# HGD_v0_1_-20200419.net
KiCad netlist of a schematic drawn in Altium Designer
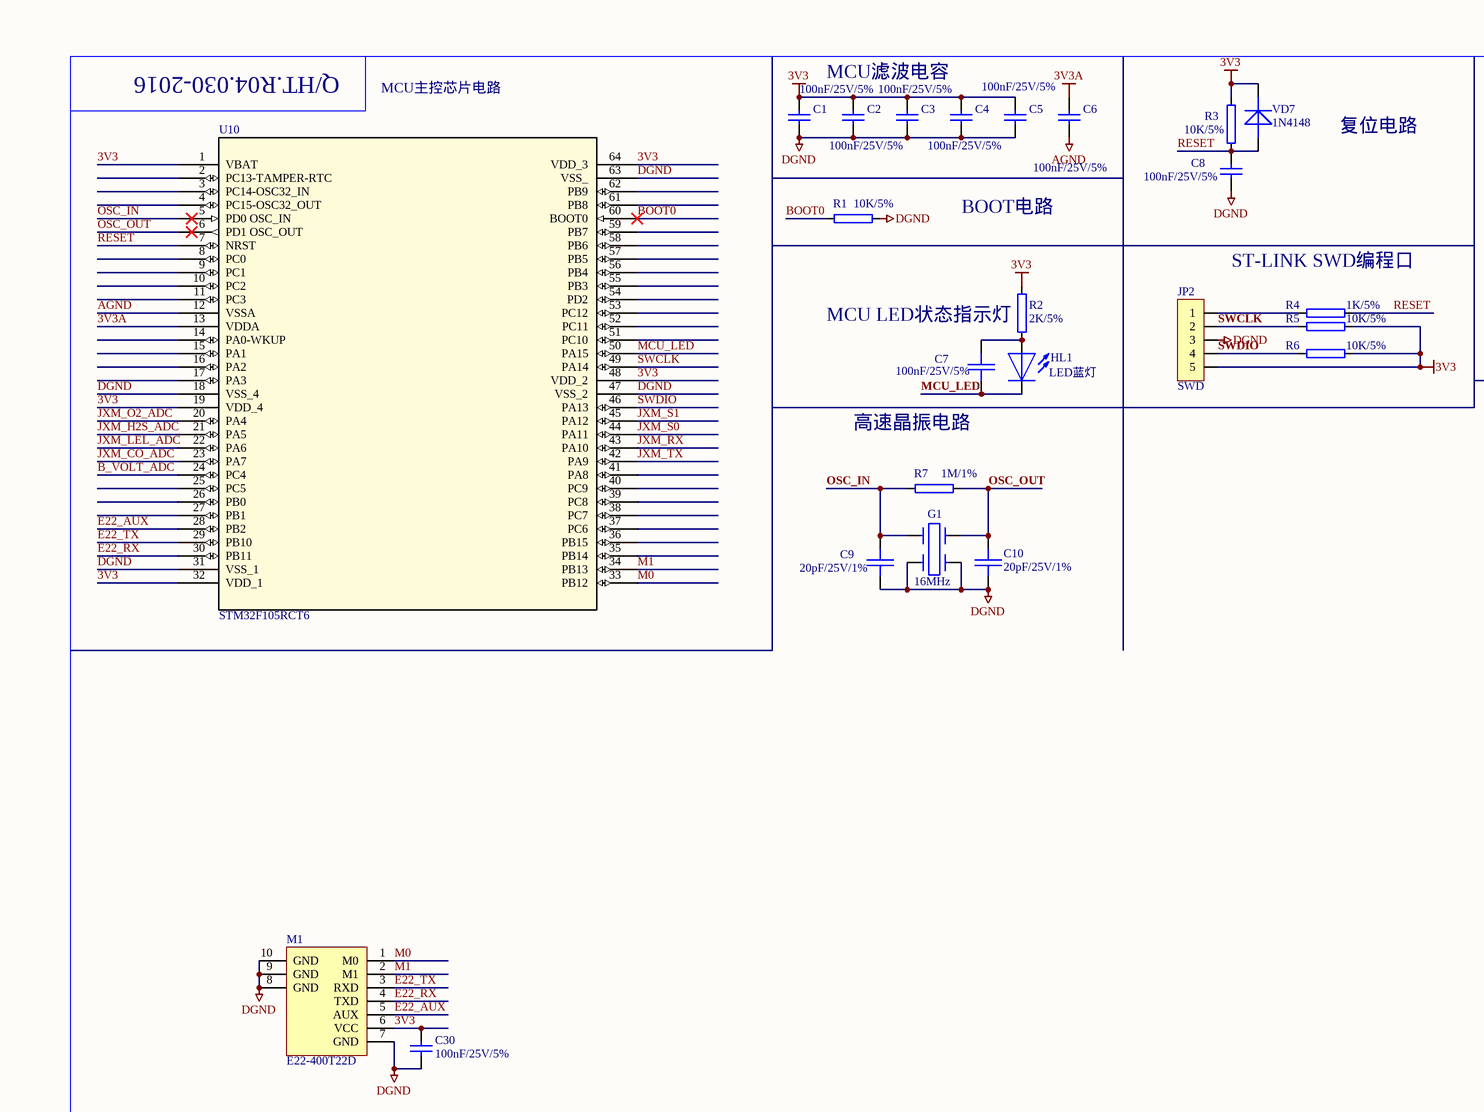
[diagram p0: HGD(v0.1)-20200419.SchDoc, top left]
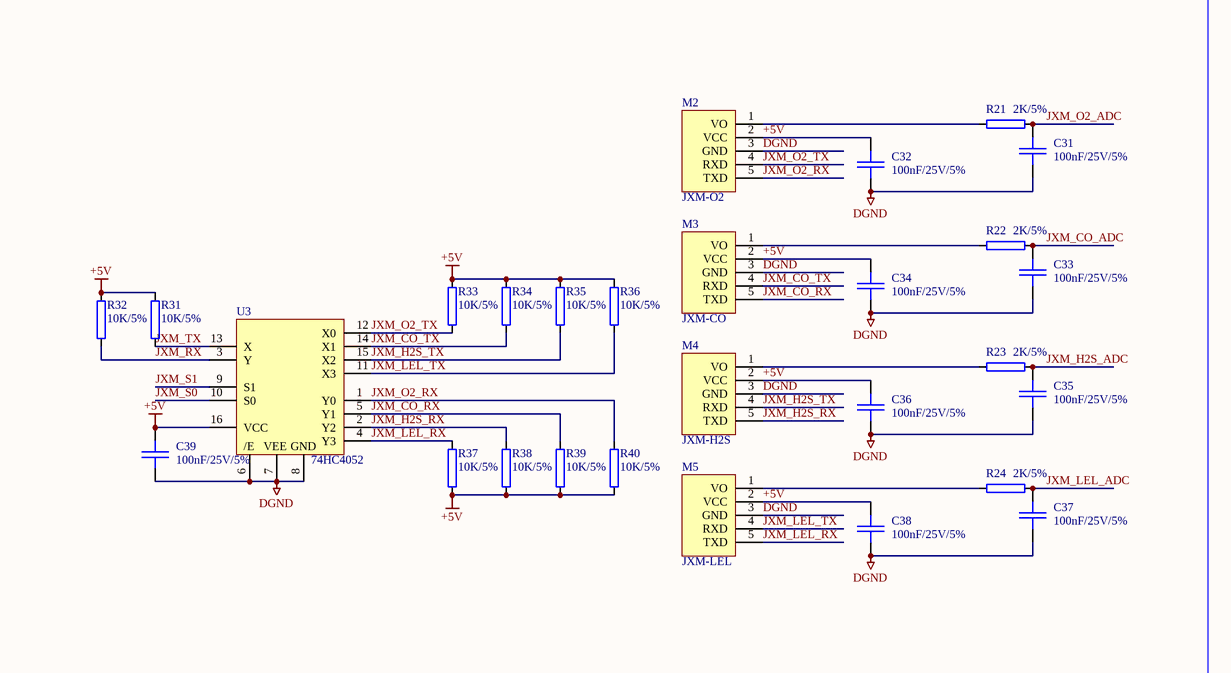
[diagram p1: HGD(v0.1)-20200419.SchDoc, top right]
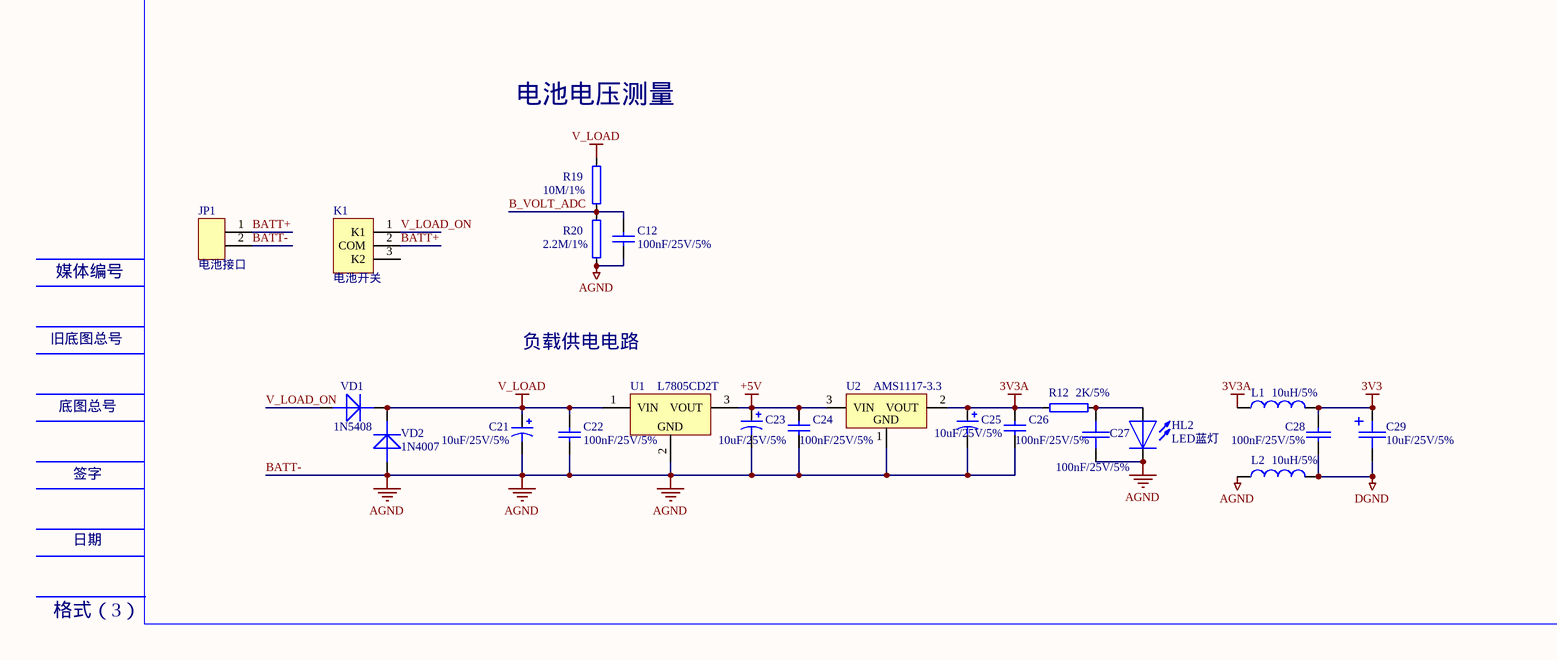
[diagram p2: HGD(v0.1)-20200419.SchDoc, bottom left]
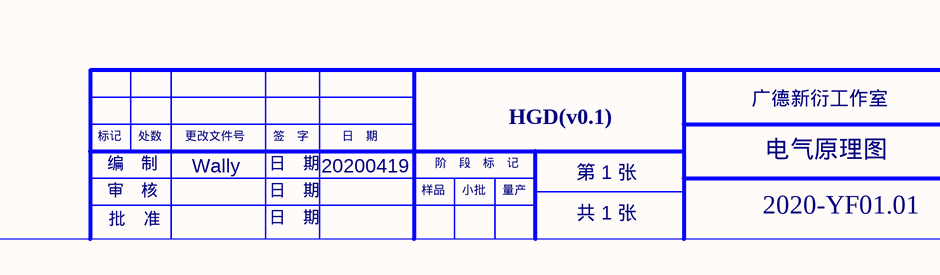
[diagram p3: HGD(v0.1)-20200419.SchDoc, bottom right]

(export (version "E")
  (design (tool "Eeschema 10.0.6"))
  (components
    (comp (ref "C1")
      (value "100nF/25V/5%")
      (footprint "C0603")
      (description "电容")
      (libsource (lib "*") (part "CAP-SMD"))
    )
    (comp (ref "C2")
      (value "100nF/25V/5%")
      (footprint "C0603")
      (description "电容")
      (libsource (lib "*") (part "CAP-SMD"))
    )
    (comp (ref "C3")
      (value "100nF/25V/5%")
      (footprint "C0603")
      (description "电容")
      (libsource (lib "*") (part "CAP-SMD"))
    )
    (comp (ref "C4")
      (value "100nF/25V/5%")
      (footprint "C0603")
      (description "电容")
      (libsource (lib "*") (part "CAP-SMD"))
    )
    (comp (ref "C5")
      (value "100nF/25V/5%")
      (footprint "C0603")
      (description "电容")
      (libsource (lib "*") (part "CAP-SMD"))
    )
    (comp (ref "C6")
      (value "100nF/25V/5%")
      (footprint "C0603")
      (description "电容")
      (libsource (lib "*") (part "CAP-SMD"))
    )
    (comp (ref "C7")
      (value "100nF/25V/5%")
      (footprint "C0603")
      (description "电容")
      (libsource (lib "*") (part "CAP"))
    )
    (comp (ref "C8")
      (value "100nF/25V/5%")
      (footprint "C0603")
      (description "电容")
      (libsource (lib "*") (part "CAP-SMD"))
    )
    (comp (ref "C9")
      (value "20pF/25V/1%")
      (footprint "C0603")
      (description "电容")
      (libsource (lib "ESSCH-Union") (part "CAP"))
    )
    (comp (ref "C10")
      (value "20pF/25V/1%")
      (footprint "C0603")
      (description "电容")
      (libsource (lib "ESSCH-Union") (part "CAP"))
    )
    (comp (ref "C12") (value "100nF/25V/5%") (footprint "C0603") (libsource (lib "*") (part "CAP-SMD")))
    (comp (ref "C21")
      (value "10uF/25V/5%")
      (footprint "C1206-1")
      (description "钽电容")
      (fields (field (name "PUBLISHER") "Altium Limited"))
      (libsource (lib "Miscellaneous Devices") (part "Cap Pol1"))
    )
    (comp (ref "C22")
      (value "100nF/25V/5%")
      (footprint "C0603")
      (description "电容")
      (fields (field (name "PUBLISHER") "Altium Limited"))
      (libsource (lib "Miscellaneous Devices") (part "Cap"))
    )
    (comp (ref "C23")
      (value "10uF/25V/5%")
      (footprint "C1206-1")
      (description "钽电容")
      (fields (field (name "PUBLISHER") "Altium Limited"))
      (libsource (lib "Miscellaneous Devices") (part "Cap Pol1"))
    )
    (comp (ref "C24")
      (value "100nF/25V/5%")
      (footprint "C0603")
      (description "电容")
      (fields (field (name "PUBLISHER") "Altium Limited"))
      (libsource (lib "Miscellaneous Devices") (part "Cap"))
    )
    (comp (ref "C25")
      (value "10uF/25V/5%")
      (footprint "C1206-1")
      (description "钽电容")
      (fields (field (name "PUBLISHER") "Altium Limited"))
      (libsource (lib "Miscellaneous Devices") (part "Cap Pol1"))
    )
    (comp (ref "C26")
      (value "100nF/25V/5%")
      (footprint "C0603")
      (description "电容")
      (fields (field (name "PUBLISHER") "Altium Limited"))
      (libsource (lib "Miscellaneous Devices") (part "Cap"))
    )
    (comp (ref "C27")
      (value "100nF/25V/5%")
      (footprint "C0603")
      (description "电容")
      (libsource (lib "*") (part "CAP"))
    )
    (comp (ref "C28")
      (value "100nF/25V/5%")
      (footprint "C0603")
      (description "电容")
      (libsource (lib "") (part "CAP_1"))
    )
    (comp (ref "C29")
      (value "10uF/25V/5%")
      (footprint "C1206-1")
      (description "钽电容")
      (libsource (lib "*") (part "ELECTRO1"))
    )
    (comp (ref "C30")
      (value "100nF/25V/5%")
      (footprint "C0603")
      (description "电容")
      (fields (field (name "PUBLISHER") "Altium Limited"))
      (libsource (lib "Miscellaneous Devices") (part "Cap"))
    )
    (comp (ref "C31")
      (value "100nF/25V/5%")
      (footprint "C0603")
      (description "电容")
      (libsource (lib "*") (part "CAP"))
    )
    (comp (ref "C32")
      (value "100nF/25V/5%")
      (footprint "C0603")
      (description "电容")
      (libsource (lib "*") (part "CAP"))
    )
    (comp (ref "C33")
      (value "100nF/25V/5%")
      (footprint "C0603")
      (description "电容")
      (libsource (lib "*") (part "CAP"))
    )
    (comp (ref "C34")
      (value "100nF/25V/5%")
      (footprint "C0603")
      (description "电容")
      (libsource (lib "*") (part "CAP"))
    )
    (comp (ref "C35")
      (value "100nF/25V/5%")
      (footprint "C0603")
      (description "电容")
      (libsource (lib "*") (part "CAP"))
    )
    (comp (ref "C36")
      (value "100nF/25V/5%")
      (footprint "C0603")
      (description "电容")
      (libsource (lib "*") (part "CAP"))
    )
    (comp (ref "C37")
      (value "100nF/25V/5%")
      (footprint "C0603")
      (description "电容")
      (libsource (lib "*") (part "CAP"))
    )
    (comp (ref "C38")
      (value "100nF/25V/5%")
      (footprint "C0603")
      (description "电容")
      (libsource (lib "*") (part "CAP"))
    )
    (comp (ref "C39")
      (value "100nF/25V/5%")
      (footprint "C0603")
      (description "电容")
      (libsource (lib "*") (part "CAP"))
    )
    (comp (ref "G1")
      (value "16MHz")
      (footprint "OSC5032")
      (description "两对电极压电晶体")
      (libsource (lib "ESSCH-Union") (part "CRYSTAL_4"))
    )
    (comp (ref "HL1")
      (value "LED蓝灯")
      (footprint "LED0603")
      (description "发光二极管")
      (libsource (lib "wypPCB_Lib") (part "发光二极管"))
    )
    (comp (ref "HL2")
      (value "LED蓝灯")
      (footprint "LED0603")
      (description "发光二极管")
      (libsource (lib "wypPCB_Lib") (part "发光二极管"))
    )
    (comp (ref "JP1")
      (value "电池接口")
      (footprint "XH2.54-LI-2P")
      (description "XH2.54-2P/PH2.0-2P插座")
      (libsource (lib "wypPCB_Lib") (part "XH2.54-2P/PH2.0-2P"))
    )
    (comp (ref "JP2")
      (value "SWD")
      (footprint "XH2.54-5AW")
      (description "XH2.54-5P直插插针")
      (libsource (lib "wypPCB_Lib") (part "JP_XH2.54-5AW"))
    )
    (comp (ref "K1")
      (value "电池开关")
      (footprint "SK-12D07")
      (description "SK-12D07：3脚2档小型拨动开关")
      (libsource (lib "wypPCB_Lib") (part "SK-12D07"))
    )
    (comp (ref "L1")
      (value "10uH/5%")
      (footprint "L0603")
      (description "电感")
      (libsource (lib "wypPCB_Lib") (part "电感"))
    )
    (comp (ref "L2")
      (value "10uH/5%")
      (footprint "L0603")
      (description "电感")
      (libsource (lib "wypPCB_Lib") (part "电感"))
    )
    (comp (ref "M1")
      (value "E22-400T22D")
      (footprint "E22-400T22D")
      (description "E22-400T22D LoRa模块")
      (libsource (lib "wypPCB_Lib") (part "E22-400T22D"))
    )
    (comp (ref "M2")
      (value "JXM-O2")
      (footprint "JXM")
      (description "JXM智能气体模组传感器")
      (libsource (lib "wypPCB_Lib") (part "JXM"))
    )
    (comp (ref "M3")
      (value "JXM-CO")
      (footprint "JXM")
      (description "JXM智能气体模组传感器")
      (libsource (lib "wypPCB_Lib") (part "JXM"))
    )
    (comp (ref "M4")
      (value "JXM-H2S")
      (footprint "JXM")
      (description "JXM智能气体模组传感器")
      (libsource (lib "wypPCB_Lib") (part "JXM"))
    )
    (comp (ref "M5")
      (value "JXM-LEL")
      (footprint "JXM")
      (description "JXM智能气体模组传感器")
      (libsource (lib "wypPCB_Lib") (part "JXM"))
    )
    (comp (ref "R1")
      (value "10K/5%")
      (footprint "R0603")
      (description "电阻")
      (libsource (lib "") (part "RES2_2"))
    )
    (comp (ref "R2")
      (value "2K/5%")
      (footprint "R0603")
      (description "电阻")
      (libsource (lib "") (part "RES2_2"))
    )
    (comp (ref "R3")
      (value "10K/5%")
      (footprint "R0603")
      (description "电阻")
      (libsource (lib "") (part "RES2_1"))
    )
    (comp (ref "R4")
      (value "1K/5%")
      (footprint "R0603")
      (description "电阻")
      (libsource (lib "") (part "RES2_1"))
    )
    (comp (ref "R5")
      (value "10K/5%")
      (footprint "R0603")
      (description "电阻")
      (libsource (lib "") (part "RES2_1"))
    )
    (comp (ref "R6")
      (value "10K/5%")
      (footprint "R0603")
      (description "电阻")
      (libsource (lib "") (part "RES2_1"))
    )
    (comp (ref "R7")
      (value "1M/1%")
      (footprint "R0603")
      (description "电阻")
      (libsource (lib "") (part "RES2_1"))
    )
    (comp (ref "R12")
      (value "2K/5%")
      (footprint "R0603")
      (description "电阻")
      (libsource (lib "") (part "RES2_2"))
    )
    (comp (ref "R19")
      (value "10M/1%")
      (footprint "R0603")
      (description "电阻")
      (libsource (lib "") (part "RES2_2"))
    )
    (comp (ref "R20")
      (value "2.2M/1%")
      (footprint "R0603")
      (description "电阻")
      (libsource (lib "") (part "RES2_2"))
    )
    (comp (ref "R21")
      (value "2K/5%")
      (footprint "R0603")
      (description "电阻")
      (libsource (lib "") (part "RES2_2"))
    )
    (comp (ref "R22")
      (value "2K/5%")
      (footprint "R0603")
      (description "电阻")
      (libsource (lib "") (part "RES2_2"))
    )
    (comp (ref "R23")
      (value "2K/5%")
      (footprint "R0603")
      (description "电阻")
      (libsource (lib "") (part "RES2_2"))
    )
    (comp (ref "R24")
      (value "2K/5%")
      (footprint "R0603")
      (description "电阻")
      (libsource (lib "") (part "RES2_2"))
    )
    (comp (ref "R31")
      (value "10K/5%")
      (footprint "R0603")
      (description "电阻")
      (libsource (lib "*") (part "RES2"))
    )
    (comp (ref "R32")
      (value "10K/5%")
      (footprint "R0603")
      (description "电阻")
      (libsource (lib "*") (part "RES2"))
    )
    (comp (ref "R33")
      (value "10K/5%")
      (footprint "R0603")
      (description "电阻")
      (libsource (lib "*") (part "RES2"))
    )
    (comp (ref "R34")
      (value "10K/5%")
      (footprint "R0603")
      (description "电阻")
      (libsource (lib "*") (part "RES2"))
    )
    (comp (ref "R35")
      (value "10K/5%")
      (footprint "R0603")
      (description "电阻")
      (libsource (lib "*") (part "RES2"))
    )
    (comp (ref "R36")
      (value "10K/5%")
      (footprint "R0603")
      (description "电阻")
      (libsource (lib "*") (part "RES2"))
    )
    (comp (ref "R37")
      (value "10K/5%")
      (footprint "R0603")
      (description "电阻")
      (libsource (lib "*") (part "RES2"))
    )
    (comp (ref "R38")
      (value "10K/5%")
      (footprint "R0603")
      (description "电阻")
      (libsource (lib "*") (part "RES2"))
    )
    (comp (ref "R39")
      (value "10K/5%")
      (footprint "R0603")
      (description "电阻")
      (libsource (lib "*") (part "RES2"))
    )
    (comp (ref "R40")
      (value "10K/5%")
      (footprint "R0603")
      (description "电阻")
      (libsource (lib "*") (part "RES2"))
    )
    (comp (ref "U1")
      (value "L7805CD2T")
      (footprint "D2PAK")
      (description "Positive voltage regulator")
      (libsource (lib "wypPCB_Lib") (part "L7805CD2T"))
    )
    (comp (ref "U2")
      (value "AMS1117-3.3")
      (footprint "SOT230P700X180-4N")
      (description "U_AMS1117稳压芯片")
      (libsource (lib "wypPCB_Lib") (part "U_AMS1117"))
    )
    (comp (ref "U3")
      (value "74HC4052")
      (footprint "SO16_74HC4052")
      (libsource (lib "wypPCB_Lib") (part "74HC4052"))
    )
    (comp (ref "U10")
      (value "STM32F105RCT6")
      (footprint "LQFP64")
      (description "MCU")
      (fields
        (field (name "MANUFACTURER_PART_NUMBER") "STM32F103RCT6")
        (field (name "DIGIKEYPARTNUMBER") "497-9033-ND")
        (field (name "COPYRIGHT") "Copyright (C) 2015 Accelerated Designs. All rights reserved")
      )
      (libsource (lib "L14-Collect_board(v1.1)") (part "STM32F103RCT6"))
    )
    (comp (ref "VD1")
      (value "1N5408")
      (footprint "SMA_DO-214AC")
      (description "开关二极管")
      (libsource (lib "wypPCB_Lib") (part "开关二极管"))
    )
    (comp (ref "VD2")
      (value "1N4007")
      (footprint "SMA_DO-214AC")
      (description "开关二极管")
      (libsource (lib "wypPCB_Lib") (part "开关二极管"))
    )
    (comp (ref "VD7")
      (value "1N4148")
      (footprint "LL-34")
      (description "开关二极管")
      (libsource (lib "wypPCB_Lib") (part "开关二极管"))
    )
  )
  (nets
    (net (code "1") (name "+5V") (class "Default")
      (node (ref "C23") (pin "1") (pinfunction "1_1") (pintype "passive"))
      (node (ref "C24") (pin "2") (pinfunction "2_2") (pintype "passive"))
      (node (ref "C32") (pin "1") (pintype "passive"))
      (node (ref "C34") (pin "1") (pintype "passive"))
      (node (ref "C36") (pin "1") (pintype "passive"))
      (node (ref "C38") (pin "1") (pintype "passive"))
      (node (ref "C39") (pin "1") (pintype "passive"))
      (node (ref "M2") (pin "2") (pinfunction "VCC_2") (pintype "passive"))
      (node (ref "M3") (pin "2") (pinfunction "VCC_2") (pintype "passive"))
      (node (ref "M4") (pin "2") (pinfunction "VCC_2") (pintype "passive"))
      (node (ref "M5") (pin "2") (pinfunction "VCC_2") (pintype "passive"))
      (node (ref "R31") (pin "2") (pintype "passive"))
      (node (ref "R32") (pin "2") (pintype "passive"))
      (node (ref "R33") (pin "2") (pintype "passive"))
      (node (ref "R34") (pin "2") (pintype "passive"))
      (node (ref "R35") (pin "2") (pintype "passive"))
      (node (ref "R36") (pin "2") (pintype "passive"))
      (node (ref "R37") (pin "1") (pintype "passive"))
      (node (ref "R38") (pin "1") (pintype "passive"))
      (node (ref "R39") (pin "1") (pintype "passive"))
      (node (ref "R40") (pin "1") (pintype "passive"))
      (node (ref "U1") (pin "3") (pinfunction "VOUT_3") (pintype "passive"))
      (node (ref "U2") (pin "3") (pinfunction "VIN_3") (pintype "passive"))
      (node (ref "U3") (pin "16") (pinfunction "VCC_16") (pintype "passive"))
    )
    (net (code "2") (name "/BATT+") (class "Default")
      (node (ref "JP1") (pin "1") (pintype "passive"))
      (node (ref "K1") (pin "2") (pinfunction "COM_2") (pintype "passive"))
    )
    (net (code "3") (name "/BOOT0") (class "Default")
      (node (ref "R1") (pin "2") (pintype "passive"))
      (node (ref "U10") (pin "60") (pinfunction "BOOT0_60") (pintype "input"))
    )
    (net (code "4") (name "/B_VOLT_ADC") (class "Default")
      (node (ref "C12") (pin "1") (pintype "passive"))
      (node (ref "R19") (pin "2") (pintype "passive"))
      (node (ref "R20") (pin "1") (pintype "passive"))
      (node (ref "U10") (pin "24") (pinfunction "PC4_24") (pintype "bidirectional"))
    )
    (net (code "5") (name "/E22_AUX") (class "Default")
      (node (ref "M1") (pin "5") (pinfunction "AUX_5") (pintype "passive"))
      (node (ref "U10") (pin "28") (pinfunction "PB2_28") (pintype "bidirectional"))
    )
    (net (code "6") (name "/E22_RX") (class "Default")
      (node (ref "M1") (pin "4") (pinfunction "TXD_4") (pintype "passive"))
      (node (ref "U10") (pin "30") (pinfunction "PB11_30") (pintype "bidirectional"))
    )
    (net (code "7") (name "/E22_TX") (class "Default")
      (node (ref "M1") (pin "3") (pinfunction "RXD_3") (pintype "passive"))
      (node (ref "U10") (pin "29") (pinfunction "PB10_29") (pintype "bidirectional"))
    )
    (net (code "8") (name "/JXM_CO_ADC") (class "Default")
      (node (ref "C33") (pin "1") (pintype "passive"))
      (node (ref "R22") (pin "1") (pintype "passive"))
      (node (ref "U10") (pin "23") (pinfunction "PA7_23") (pintype "bidirectional"))
    )
    (net (code "9") (name "/JXM_CO_RX") (class "Default")
      (node (ref "M3") (pin "5") (pinfunction "TXD_5") (pintype "passive"))
      (node (ref "R39") (pin "2") (pintype "passive"))
      (node (ref "U3") (pin "5") (pinfunction "Y1_5") (pintype "passive"))
    )
    (net (code "10") (name "/JXM_CO_TX") (class "Default")
      (node (ref "M3") (pin "4") (pinfunction "RXD_4") (pintype "passive"))
      (node (ref "R34") (pin "1") (pintype "passive"))
      (node (ref "U3") (pin "14") (pinfunction "X1_14") (pintype "passive"))
    )
    (net (code "11") (name "/JXM_H2S_ADC") (class "Default")
      (node (ref "C35") (pin "1") (pintype "passive"))
      (node (ref "R23") (pin "1") (pintype "passive"))
      (node (ref "U10") (pin "21") (pinfunction "PA5_21") (pintype "bidirectional"))
    )
    (net (code "12") (name "/JXM_H2S_RX") (class "Default")
      (node (ref "M4") (pin "5") (pinfunction "TXD_5") (pintype "passive"))
      (node (ref "R38") (pin "2") (pintype "passive"))
      (node (ref "U3") (pin "2") (pinfunction "Y2_2") (pintype "passive"))
    )
    (net (code "13") (name "/JXM_H2S_TX") (class "Default")
      (node (ref "M4") (pin "4") (pinfunction "RXD_4") (pintype "passive"))
      (node (ref "R35") (pin "1") (pintype "passive"))
      (node (ref "U3") (pin "15") (pinfunction "X2_15") (pintype "passive"))
    )
    (net (code "14") (name "/JXM_LEL_ADC") (class "Default")
      (node (ref "C37") (pin "1") (pintype "passive"))
      (node (ref "R24") (pin "1") (pintype "passive"))
      (node (ref "U10") (pin "22") (pinfunction "PA6_22") (pintype "bidirectional"))
    )
    (net (code "15") (name "/JXM_LEL_RX") (class "Default")
      (node (ref "M5") (pin "5") (pinfunction "TXD_5") (pintype "passive"))
      (node (ref "R37") (pin "2") (pintype "passive"))
      (node (ref "U3") (pin "4") (pinfunction "Y3_4") (pintype "passive"))
    )
    (net (code "16") (name "/JXM_LEL_TX") (class "Default")
      (node (ref "M5") (pin "4") (pinfunction "RXD_4") (pintype "passive"))
      (node (ref "R36") (pin "1") (pintype "passive"))
      (node (ref "U3") (pin "11") (pinfunction "X3_11") (pintype "passive"))
    )
    (net (code "17") (name "/JXM_O2_ADC") (class "Default")
      (node (ref "C31") (pin "1") (pintype "passive"))
      (node (ref "R21") (pin "1") (pintype "passive"))
      (node (ref "U10") (pin "20") (pinfunction "PA4_20") (pintype "bidirectional"))
    )
    (net (code "18") (name "/JXM_O2_RX") (class "Default")
      (node (ref "M2") (pin "5") (pinfunction "TXD_5") (pintype "passive"))
      (node (ref "R40") (pin "2") (pintype "passive"))
      (node (ref "U3") (pin "1") (pinfunction "Y0_1") (pintype "passive"))
    )
    (net (code "19") (name "/JXM_O2_TX") (class "Default")
      (node (ref "M2") (pin "4") (pinfunction "RXD_4") (pintype "passive"))
      (node (ref "R33") (pin "1") (pintype "passive"))
      (node (ref "U3") (pin "12") (pinfunction "X0_12") (pintype "passive"))
    )
    (net (code "20") (name "/JXM_RX") (class "Default")
      (node (ref "R32") (pin "1") (pintype "passive"))
      (node (ref "U10") (pin "43") (pinfunction "PA10_43") (pintype "bidirectional"))
      (node (ref "U3") (pin "3") (pinfunction "Y_3") (pintype "passive"))
    )
    (net (code "21") (name "/JXM_S0") (class "Default")
      (node (ref "U10") (pin "44") (pinfunction "PA11_44") (pintype "bidirectional"))
      (node (ref "U3") (pin "10") (pinfunction "S0_10") (pintype "passive"))
    )
    (net (code "22") (name "/JXM_S1") (class "Default")
      (node (ref "U10") (pin "45") (pinfunction "PA12_45") (pintype "bidirectional"))
      (node (ref "U3") (pin "9") (pinfunction "S1_9") (pintype "passive"))
    )
    (net (code "23") (name "/JXM_TX") (class "Default")
      (node (ref "R31") (pin "1") (pintype "passive"))
      (node (ref "U10") (pin "42") (pinfunction "PA9_42") (pintype "bidirectional"))
      (node (ref "U3") (pin "13") (pinfunction "X_13") (pintype "passive"))
    )
    (net (code "24") (name "/M0") (class "Default")
      (node (ref "M1") (pin "1") (pinfunction "M0_1") (pintype "passive"))
      (node (ref "U10") (pin "33") (pinfunction "PB12_33") (pintype "bidirectional"))
    )
    (net (code "25") (name "/M1") (class "Default")
      (node (ref "M1") (pin "2") (pinfunction "M1_2") (pintype "passive"))
      (node (ref "U10") (pin "34") (pinfunction "PB13_34") (pintype "bidirectional"))
    )
    (net (code "26") (name "/MCU_LED") (class "Default")
      (node (ref "C7") (pin "2") (pintype "passive"))
      (node (ref "HL1") (pin "K") (pintype "passive"))
      (node (ref "U10") (pin "50") (pinfunction "PA15_50") (pintype "bidirectional"))
    )
    (net (code "27") (name "/OSC_IN") (class "Default")
      (node (ref "C9") (pin "2") (pintype "passive"))
      (node (ref "G1") (pin "1") (pintype "passive"))
      (node (ref "R7") (pin "1") (pintype "passive"))
      (node (ref "U10") (pin "5") (pinfunction "PD0_OSC_IN_5") (pintype "input"))
    )
    (net (code "28") (name "/OSC_OUT") (class "Default")
      (node (ref "C10") (pin "1") (pintype "passive"))
      (node (ref "G1") (pin "3") (pintype "passive"))
      (node (ref "R7") (pin "2") (pintype "passive"))
      (node (ref "U10") (pin "6") (pinfunction "PD1_OSC_OUT_6") (pintype "output"))
    )
    (net (code "29") (name "/RESET") (class "Default")
      (node (ref "C8") (pin "1") (pintype "passive"))
      (node (ref "R3") (pin "1") (pintype "passive"))
      (node (ref "R4") (pin "2") (pintype "passive"))
      (node (ref "U10") (pin "7") (pinfunction "NRST_7") (pintype "bidirectional"))
      (node (ref "VD7") (pin "A") (pintype "passive"))
    )
    (net (code "30") (name "/SWCLK") (class "Default")
      (node (ref "JP2") (pin "2") (pinfunction "2_2") (pintype "passive"))
      (node (ref "R5") (pin "1") (pintype "passive"))
      (node (ref "U10") (pin "49") (pinfunction "PA14_49") (pintype "bidirectional"))
    )
    (net (code "31") (name "/SWDIO") (class "Default")
      (node (ref "JP2") (pin "4") (pinfunction "4_4") (pintype "passive"))
      (node (ref "R6") (pin "1") (pintype "passive"))
      (node (ref "U10") (pin "46") (pinfunction "PA13_46") (pintype "bidirectional"))
    )
    (net (code "32") (name "/V_LOAD_ON") (class "Default")
      (node (ref "K1") (pin "1") (pinfunction "K1_1") (pintype "passive"))
      (node (ref "VD1") (pin "A") (pintype "passive"))
    )
    (net (code "33") (name "3V3") (class "Default")
      (node (ref "C1") (pin "2") (pintype "passive"))
      (node (ref "C2") (pin "1") (pintype "passive"))
      (node (ref "C28") (pin "2") (pintype "passive"))
      (node (ref "C29") (pin "1") (pintype "passive"))
      (node (ref "C3") (pin "1") (pintype "passive"))
      (node (ref "C30") (pin "2") (pinfunction "2_2") (pintype "passive"))
      (node (ref "C4") (pin "2") (pintype "passive"))
      (node (ref "C5") (pin "2") (pintype "passive"))
      (node (ref "JP2") (pin "5") (pinfunction "5_5") (pintype "passive"))
      (node (ref "L1") (pin "2") (pinfunction "2_2") (pintype "passive"))
      (node (ref "M1") (pin "6") (pinfunction "VCC_6") (pintype "passive"))
      (node (ref "R2") (pin "1") (pintype "passive"))
      (node (ref "R3") (pin "2") (pintype "passive"))
      (node (ref "R5") (pin "2") (pintype "passive"))
      (node (ref "R6") (pin "2") (pintype "passive"))
      (node (ref "U10") (pin "1") (pinfunction "VBAT_1") (pintype "power_in"))
      (node (ref "U10") (pin "19") (pinfunction "VDD_4_19") (pintype "power_in"))
      (node (ref "U10") (pin "32") (pinfunction "VDD_1_32") (pintype "power_in"))
      (node (ref "U10") (pin "48") (pinfunction "VDD_2_48") (pintype "power_in"))
      (node (ref "U10") (pin "64") (pinfunction "VDD_3_64") (pintype "power_in"))
      (node (ref "VD7") (pin "K") (pintype "passive"))
    )
    (net (code "34") (name "3V3A") (class "Default")
      (node (ref "C25") (pin "1") (pinfunction "1_1") (pintype "passive"))
      (node (ref "C26") (pin "2") (pinfunction "2_2") (pintype "passive"))
      (node (ref "C6") (pin "2") (pintype "passive"))
      (node (ref "L1") (pin "1") (pinfunction "1_1") (pintype "passive"))
      (node (ref "R12") (pin "1") (pintype "passive"))
      (node (ref "U10") (pin "13") (pinfunction "VDDA_13") (pintype "power_in"))
      (node (ref "U2") (pin "2") (pinfunction "VOUT_2") (pintype "passive"))
    )
    (net (code "35") (name "AGND") (class "Default")
      (node (ref "C12") (pin "2") (pintype "passive"))
      (node (ref "C21") (pin "2") (pinfunction "2_2") (pintype "passive"))
      (node (ref "C22") (pin "1") (pinfunction "1_1") (pintype "passive"))
      (node (ref "C23") (pin "2") (pinfunction "2_2") (pintype "passive"))
      (node (ref "C24") (pin "1") (pinfunction "1_1") (pintype "passive"))
      (node (ref "C25") (pin "2") (pinfunction "2_2") (pintype "passive"))
      (node (ref "C26") (pin "1") (pinfunction "1_1") (pintype "passive"))
      (node (ref "C27") (pin "2") (pintype "passive"))
      (node (ref "C6") (pin "1") (pintype "passive"))
      (node (ref "HL2") (pin "K") (pintype "passive"))
      (node (ref "JP1") (pin "2") (pintype "passive"))
      (node (ref "L2") (pin "1") (pinfunction "1_1") (pintype "passive"))
      (node (ref "R20") (pin "2") (pintype "passive"))
      (node (ref "U1") (pin "2") (pinfunction "GND_2") (pintype "passive"))
      (node (ref "U10") (pin "12") (pinfunction "VSSA_12") (pintype "power_in"))
      (node (ref "U2") (pin "1") (pinfunction "GND_1") (pintype "passive"))
      (node (ref "VD2") (pin "A") (pintype "passive"))
    )
    (net (code "36") (name "DGND") (class "Default")
      (node (ref "C1") (pin "1") (pintype "passive"))
      (node (ref "C10") (pin "2") (pintype "passive"))
      (node (ref "C2") (pin "2") (pintype "passive"))
      (node (ref "C28") (pin "1") (pintype "passive"))
      (node (ref "C29") (pin "2") (pintype "passive"))
      (node (ref "C3") (pin "2") (pintype "passive"))
      (node (ref "C30") (pin "1") (pinfunction "1_1") (pintype "passive"))
      (node (ref "C31") (pin "2") (pintype "passive"))
      (node (ref "C32") (pin "2") (pintype "passive"))
      (node (ref "C33") (pin "2") (pintype "passive"))
      (node (ref "C34") (pin "2") (pintype "passive"))
      (node (ref "C35") (pin "2") (pintype "passive"))
      (node (ref "C36") (pin "2") (pintype "passive"))
      (node (ref "C37") (pin "2") (pintype "passive"))
      (node (ref "C38") (pin "2") (pintype "passive"))
      (node (ref "C39") (pin "2") (pintype "passive"))
      (node (ref "C4") (pin "1") (pintype "passive"))
      (node (ref "C5") (pin "1") (pintype "passive"))
      (node (ref "C8") (pin "2") (pintype "passive"))
      (node (ref "C9") (pin "1") (pintype "passive"))
      (node (ref "G1") (pin "2") (pintype "passive"))
      (node (ref "G1") (pin "4") (pintype "passive"))
      (node (ref "JP2") (pin "3") (pinfunction "3_3") (pintype "passive"))
      (node (ref "L2") (pin "2") (pinfunction "2_2") (pintype "passive"))
      (node (ref "M1") (pin "10") (pinfunction "GND_10") (pintype "passive"))
      (node (ref "M1") (pin "7") (pinfunction "GND_7") (pintype "passive"))
      (node (ref "M1") (pin "8") (pinfunction "GND_8") (pintype "passive"))
      (node (ref "M1") (pin "9") (pinfunction "GND_9") (pintype "passive"))
      (node (ref "M2") (pin "3") (pinfunction "GND_3") (pintype "passive"))
      (node (ref "M3") (pin "3") (pinfunction "GND_3") (pintype "passive"))
      (node (ref "M4") (pin "3") (pinfunction "GND_3") (pintype "passive"))
      (node (ref "M5") (pin "3") (pinfunction "GND_3") (pintype "passive"))
      (node (ref "R1") (pin "1") (pintype "passive"))
      (node (ref "U10") (pin "18") (pinfunction "VSS_4_18") (pintype "power_in"))
      (node (ref "U10") (pin "31") (pinfunction "VSS_1_31") (pintype "power_in"))
      (node (ref "U10") (pin "47") (pinfunction "VSS_2_47") (pintype "power_in"))
      (node (ref "U10") (pin "63") (pinfunction "VSS__63") (pintype "power_in"))
      (node (ref "U3") (pin "6") (pinfunction "~{E}_6") (pintype "passive"))
      (node (ref "U3") (pin "7") (pinfunction "VEE_7") (pintype "passive"))
      (node (ref "U3") (pin "8") (pinfunction "GND_8") (pintype "passive"))
    )
    (net (code "37") (name "Net-(C7-Pad1)") (class "Default")
      (node (ref "C7") (pin "1") (pintype "passive"))
      (node (ref "HL1") (pin "A") (pintype "passive"))
      (node (ref "R2") (pin "2") (pintype "passive"))
    )
    (net (code "38") (name "Net-(C27-Pad1)") (class "Default")
      (node (ref "C27") (pin "1") (pintype "passive"))
      (node (ref "HL2") (pin "A") (pintype "passive"))
      (node (ref "R12") (pin "2") (pintype "passive"))
    )
    (net (code "39") (name "Net-(JP2-Pad1)") (class "Default")
      (node (ref "JP2") (pin "1") (pinfunction "1_1") (pintype "passive"))
      (node (ref "R4") (pin "1") (pintype "passive"))
    )
    (net (code "40") (name "Net-(M2-VO)") (class "Default")
      (node (ref "M2") (pin "1") (pinfunction "VO_1") (pintype "passive"))
      (node (ref "R21") (pin "2") (pintype "passive"))
    )
    (net (code "41") (name "Net-(M3-VO)") (class "Default")
      (node (ref "M3") (pin "1") (pinfunction "VO_1") (pintype "passive"))
      (node (ref "R22") (pin "2") (pintype "passive"))
    )
    (net (code "42") (name "Net-(M4-VO)") (class "Default")
      (node (ref "M4") (pin "1") (pinfunction "VO_1") (pintype "passive"))
      (node (ref "R23") (pin "2") (pintype "passive"))
    )
    (net (code "43") (name "Net-(M5-VO)") (class "Default")
      (node (ref "M5") (pin "1") (pinfunction "VO_1") (pintype "passive"))
      (node (ref "R24") (pin "2") (pintype "passive"))
    )
    (net (code "44") (name "V_LOAD") (class "Default")
      (node (ref "C21") (pin "1") (pinfunction "1_1") (pintype "passive"))
      (node (ref "C22") (pin "2") (pinfunction "2_2") (pintype "passive"))
      (node (ref "R19") (pin "1") (pintype "passive"))
      (node (ref "U1") (pin "1") (pinfunction "VIN_1") (pintype "passive"))
      (node (ref "VD1") (pin "K") (pintype "passive"))
      (node (ref "VD2") (pin "K") (pintype "passive"))
    )
    (net (code "45") (name "unconnected-(K1-K2-Pad3)") (class "Default")
      (node (ref "K1") (pin "3") (pinfunction "K2_3") (pintype "passive"))
    )
    (net (code "46") (name "unconnected-(U10-PA0-WKUP-Pad14)") (class "Default")
      (node (ref "U10") (pin "14") (pinfunction "PA0-WKUP_14") (pintype "bidirectional"))
    )
    (net (code "47") (name "unconnected-(U10-PA1-Pad15)") (class "Default")
      (node (ref "U10") (pin "15") (pinfunction "PA1_15") (pintype "bidirectional"))
    )
    (net (code "48") (name "unconnected-(U10-PA2-Pad16)") (class "Default")
      (node (ref "U10") (pin "16") (pinfunction "PA2_16") (pintype "bidirectional"))
    )
    (net (code "49") (name "unconnected-(U10-PA3-Pad17)") (class "Default")
      (node (ref "U10") (pin "17") (pinfunction "PA3_17") (pintype "bidirectional"))
    )
    (net (code "50") (name "unconnected-(U10-PA8-Pad41)") (class "Default")
      (node (ref "U10") (pin "41") (pinfunction "PA8_41") (pintype "bidirectional"))
    )
    (net (code "51") (name "unconnected-(U10-PB0-Pad26)") (class "Default")
      (node (ref "U10") (pin "26") (pinfunction "PB0_26") (pintype "bidirectional"))
    )
    (net (code "52") (name "unconnected-(U10-PB1-Pad27)") (class "Default")
      (node (ref "U10") (pin "27") (pinfunction "PB1_27") (pintype "bidirectional"))
    )
    (net (code "53") (name "unconnected-(U10-PB3-Pad55)") (class "Default")
      (node (ref "U10") (pin "55") (pinfunction "PB3_55") (pintype "bidirectional"))
    )
    (net (code "54") (name "unconnected-(U10-PB4-Pad56)") (class "Default")
      (node (ref "U10") (pin "56") (pinfunction "PB4_56") (pintype "bidirectional"))
    )
    (net (code "55") (name "unconnected-(U10-PB5-Pad57)") (class "Default")
      (node (ref "U10") (pin "57") (pinfunction "PB5_57") (pintype "bidirectional"))
    )
    (net (code "56") (name "unconnected-(U10-PB6-Pad58)") (class "Default")
      (node (ref "U10") (pin "58") (pinfunction "PB6_58") (pintype "bidirectional"))
    )
    (net (code "57") (name "unconnected-(U10-PB7-Pad59)") (class "Default")
      (node (ref "U10") (pin "59") (pinfunction "PB7_59") (pintype "bidirectional"))
    )
    (net (code "58") (name "unconnected-(U10-PB8-Pad61)") (class "Default")
      (node (ref "U10") (pin "61") (pinfunction "PB8_61") (pintype "bidirectional"))
    )
    (net (code "59") (name "unconnected-(U10-PB9-Pad62)") (class "Default")
      (node (ref "U10") (pin "62") (pinfunction "PB9_62") (pintype "bidirectional"))
    )
    (net (code "60") (name "unconnected-(U10-PB14-Pad35)") (class "Default")
      (node (ref "U10") (pin "35") (pinfunction "PB14_35") (pintype "bidirectional"))
    )
    (net (code "61") (name "unconnected-(U10-PB15-Pad36)") (class "Default")
      (node (ref "U10") (pin "36") (pinfunction "PB15_36") (pintype "bidirectional"))
    )
    (net (code "62") (name "unconnected-(U10-PC0-Pad8)") (class "Default")
      (node (ref "U10") (pin "8") (pinfunction "PC0_8") (pintype "bidirectional"))
    )
    (net (code "63") (name "unconnected-(U10-PC1-Pad9)") (class "Default")
      (node (ref "U10") (pin "9") (pinfunction "PC1_9") (pintype "bidirectional"))
    )
    (net (code "64") (name "unconnected-(U10-PC2-Pad10)") (class "Default")
      (node (ref "U10") (pin "10") (pinfunction "PC2_10") (pintype "bidirectional"))
    )
    (net (code "65") (name "unconnected-(U10-PC3-Pad11)") (class "Default")
      (node (ref "U10") (pin "11") (pinfunction "PC3_11") (pintype "bidirectional"))
    )
    (net (code "66") (name "unconnected-(U10-PC5-Pad25)") (class "Default")
      (node (ref "U10") (pin "25") (pinfunction "PC5_25") (pintype "bidirectional"))
    )
    (net (code "67") (name "unconnected-(U10-PC6-Pad37)") (class "Default")
      (node (ref "U10") (pin "37") (pinfunction "PC6_37") (pintype "bidirectional"))
    )
    (net (code "68") (name "unconnected-(U10-PC7-Pad38)") (class "Default")
      (node (ref "U10") (pin "38") (pinfunction "PC7_38") (pintype "bidirectional"))
    )
    (net (code "69") (name "unconnected-(U10-PC8-Pad39)") (class "Default")
      (node (ref "U10") (pin "39") (pinfunction "PC8_39") (pintype "bidirectional"))
    )
    (net (code "70") (name "unconnected-(U10-PC9-Pad40)") (class "Default")
      (node (ref "U10") (pin "40") (pinfunction "PC9_40") (pintype "bidirectional"))
    )
    (net (code "71") (name "unconnected-(U10-PC10-Pad51)") (class "Default")
      (node (ref "U10") (pin "51") (pinfunction "PC10_51") (pintype "bidirectional"))
    )
    (net (code "72") (name "unconnected-(U10-PC11-Pad52)") (class "Default")
      (node (ref "U10") (pin "52") (pinfunction "PC11_52") (pintype "bidirectional"))
    )
    (net (code "73") (name "unconnected-(U10-PC12-Pad53)") (class "Default")
      (node (ref "U10") (pin "53") (pinfunction "PC12_53") (pintype "bidirectional"))
    )
    (net (code "74") (name "unconnected-(U10-PC13-TAMPER-RTC-Pad2)") (class "Default")
      (node (ref "U10") (pin "2") (pinfunction "PC13-TAMPER-RTC_2") (pintype "bidirectional"))
    )
    (net (code "75") (name "unconnected-(U10-PC14-OSC32_IN-Pad3)") (class "Default")
      (node (ref "U10") (pin "3") (pinfunction "PC14-OSC32_IN_3") (pintype "bidirectional"))
    )
    (net (code "76") (name "unconnected-(U10-PC15-OSC32_OUT-Pad4)") (class "Default")
      (node (ref "U10") (pin "4") (pinfunction "PC15-OSC32_OUT_4") (pintype "bidirectional"))
    )
    (net (code "77") (name "unconnected-(U10-PD2-Pad54)") (class "Default")
      (node (ref "U10") (pin "54") (pinfunction "PD2_54") (pintype "bidirectional"))
    )
  )
)
